# 03_-_NDP_LRA_and_BLE.net
KiCad netlist of a schematic drawn in Altium Designer
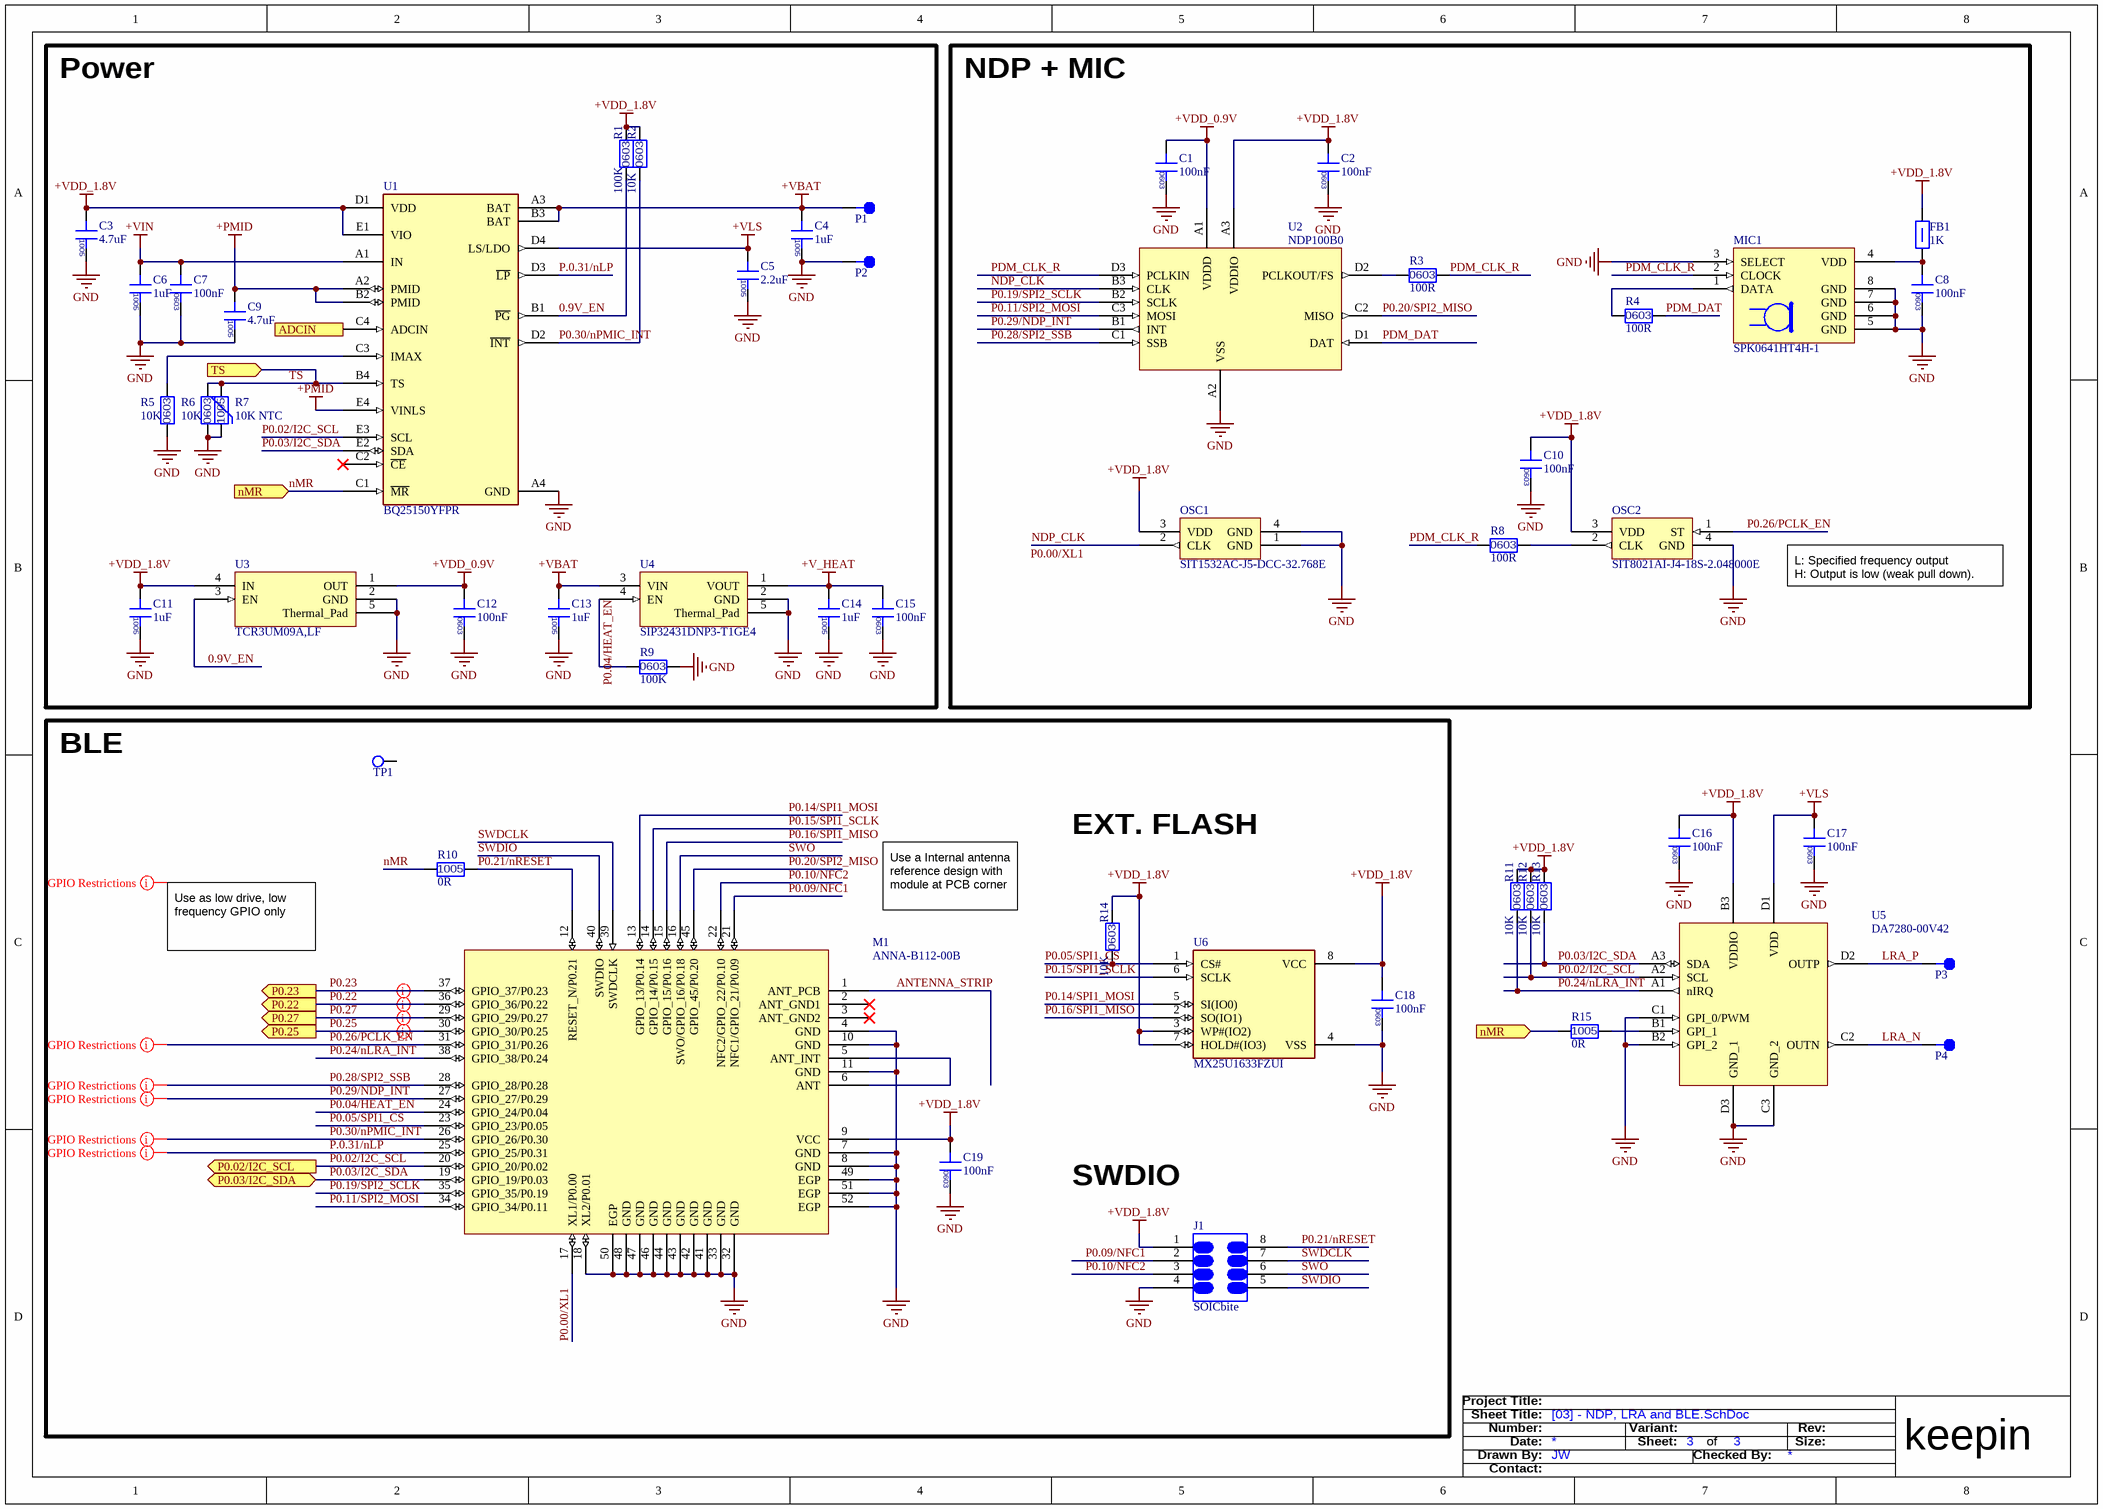
[diagram p0: [03] - NDP, LRA and BLE.SchDoc]

(export (version "E")
  (design (tool "Eeschema 10.0.6"))
  (components
    (comp (ref "C1")
      (value "100nF")
      (footprint "CAPC0603X03N")
      (description "CAP CER 0.1UF 16V X7S 0201")
      (fields
        (field (name "MANUFACTURER") "Murata")
        (field (name "MANUFACTURER PART NUMBER") "GRM033C71C104ME14D")
      )
      (libsource (lib "Schlib-master") (part "GRM033C71C104ME14D"))
    )
    (comp (ref "C2")
      (value "100nF")
      (footprint "CAPC0603X03N")
      (description "CAP CER 0.1UF 16V X7S 0201")
      (fields
        (field (name "MANUFACTURER") "Murata")
        (field (name "MANUFACTURER PART NUMBER") "GRM033C71C104ME14D")
      )
      (libsource (lib "Schlib-master") (part "GRM033C71C104ME14D"))
    )
    (comp (ref "C3")
      (value "4.7uF")
      (footprint "CAPC1005X06N")
      (description "CAP CER 4.7UF 16V X5R 0402")
      (fields (field (name "TOLERANCE") "20%") (field (name "MANUFACTURER") "Samsung"))
      (libsource (lib "Schlib-master") (part "CL05A475MO5NUNC"))
    )
    (comp (ref "C4")
      (value "1uF")
      (footprint "CAPC1005X06N")
      (description "CAP CER 1UF 16V X5R 0402")
      (fields
        (field (name "MANUFACTURER") "Samsung")
        (field (name "MANUFACTURER PART NUMBER") "CL05A105KO5NNNC")
      )
      (libsource (lib "Schlib-master") (part "CL05A105KO5NNNC"))
    )
    (comp (ref "C5")
      (value "2.2uF")
      (footprint "CAPC1005X06N")
      (description "CAP CER 2.2UF 10V X5R 0402")
      (fields
        (field (name "MANUFACTURER") "Samsung")
        (field (name "MANUFACTURER PART NUMBER") "CL05A225KP7NSB8")
      )
      (libsource (lib "Schlib-master") (part "CL05A225KP7NSB8"))
    )
    (comp (ref "C6")
      (value "1uF")
      (footprint "CAPC1005X06N")
      (description "CAP CER 1UF 16V X5R 0402")
      (fields
        (field (name "MANUFACTURER") "Samsung")
        (field (name "MANUFACTURER PART NUMBER") "CL05A105KO5NNNC")
      )
      (libsource (lib "Schlib-master") (part "CL05A105KO5NNNC"))
    )
    (comp (ref "C7")
      (value "100nF")
      (footprint "CAPC0603X03N")
      (description "CAP CER 0.1UF 16V X7S 0201")
      (fields
        (field (name "MANUFACTURER") "Murata")
        (field (name "MANUFACTURER PART NUMBER") "GRM033C71C104ME14D")
      )
      (libsource (lib "Schlib-master") (part "GRM033C71C104ME14D"))
    )
    (comp (ref "C8")
      (value "100nF")
      (footprint "CAPC0603X03N")
      (description "CAP CER 0.1UF 16V X7S 0201")
      (fields
        (field (name "MANUFACTURER") "Murata")
        (field (name "MANUFACTURER PART NUMBER") "GRM033C71C104ME14D")
      )
      (libsource (lib "Schlib-master") (part "GRM033C71C104ME14D"))
    )
    (comp (ref "C9")
      (value "4.7uF")
      (footprint "CAPC1005X06N")
      (description "CAP CER 4.7UF 16V X5R 0402")
      (fields (field (name "TOLERANCE") "20%") (field (name "MANUFACTURER") "Samsung"))
      (libsource (lib "Schlib-master") (part "CL05A475MO5NUNC"))
    )
    (comp (ref "C10")
      (value "100nF")
      (footprint "CAPC0603X03N")
      (description "CAP CER 0.1UF 16V X7S 0201")
      (fields
        (field (name "MANUFACTURER") "Murata")
        (field (name "MANUFACTURER PART NUMBER") "GRM033C71C104ME14D")
      )
      (libsource (lib "Schlib-master") (part "GRM033C71C104ME14D"))
    )
    (comp (ref "C11")
      (value "1uF")
      (footprint "CAPC1005X06N")
      (description "CAP CER 1UF 16V X5R 0402")
      (fields
        (field (name "MANUFACTURER") "Samsung")
        (field (name "MANUFACTURER PART NUMBER") "CL05A105KO5NNNC")
      )
      (libsource (lib "Schlib-master") (part "CL05A105KO5NNNC"))
    )
    (comp (ref "C12")
      (value "100nF")
      (footprint "CAPC0603X03N")
      (description "CAP CER 0.1UF 16V X7S 0201")
      (fields
        (field (name "MANUFACTURER") "Murata")
        (field (name "MANUFACTURER PART NUMBER") "GRM033C71C104ME14D")
      )
      (libsource (lib "Schlib-master") (part "GRM033C71C104ME14D"))
    )
    (comp (ref "C13")
      (value "1uF")
      (footprint "CAPC1005X06N")
      (description "CAP CER 1UF 16V X5R 0402")
      (fields
        (field (name "MANUFACTURER") "Samsung")
        (field (name "MANUFACTURER PART NUMBER") "CL05A105KO5NNNC")
      )
      (libsource (lib "Schlib-master") (part "CL05A105KO5NNNC"))
    )
    (comp (ref "C14")
      (value "1uF")
      (footprint "CAPC1005X06N")
      (description "CAP CER 1UF 16V X5R 0402")
      (fields
        (field (name "MANUFACTURER") "Samsung")
        (field (name "MANUFACTURER PART NUMBER") "CL05A105KO5NNNC")
      )
      (libsource (lib "Schlib-master") (part "CL05A105KO5NNNC"))
    )
    (comp (ref "C15")
      (value "100nF")
      (footprint "CAPC0603X03N")
      (description "CAP CER 0.1UF 16V X7S 0201")
      (fields
        (field (name "MANUFACTURER") "Murata")
        (field (name "MANUFACTURER PART NUMBER") "GRM033C71C104ME14D")
      )
      (libsource (lib "Schlib-master") (part "GRM033C71C104ME14D"))
    )
    (comp (ref "C16")
      (value "100nF")
      (footprint "CAPC0603X03N")
      (description "CAP CER 0.1UF 16V X7S 0201")
      (fields
        (field (name "MANUFACTURER") "Murata")
        (field (name "MANUFACTURER PART NUMBER") "GRM033C71C104ME14D")
      )
      (libsource (lib "Schlib-master") (part "GRM033C71C104ME14D"))
    )
    (comp (ref "C17")
      (value "100nF")
      (footprint "CAPC0603X03N")
      (description "CAP CER 0.1UF 16V X7S 0201")
      (fields
        (field (name "MANUFACTURER") "Murata")
        (field (name "MANUFACTURER PART NUMBER") "GRM033C71C104ME14D")
      )
      (libsource (lib "Schlib-master") (part "GRM033C71C104ME14D"))
    )
    (comp (ref "C18")
      (value "100nF")
      (footprint "CAPC0603X03N")
      (description "CAP CER 0.1UF 16V X7S 0201")
      (fields
        (field (name "MANUFACTURER") "Murata")
        (field (name "MANUFACTURER PART NUMBER") "GRM033C71C104ME14D")
      )
      (libsource (lib "Schlib-master") (part "GRM033C71C104ME14D"))
    )
    (comp (ref "C19")
      (value "100nF")
      (footprint "CAPC0603X03N")
      (description "CAP CER 0.1UF 16V X7S 0201")
      (fields
        (field (name "MANUFACTURER") "Murata")
        (field (name "MANUFACTURER PART NUMBER") "GRM033C71C104ME14D")
      )
      (libsource (lib "Schlib-master") (part "GRM033C71C104ME14D"))
    )
    (comp (ref "FB1")
      (value "1K")
      (footprint "INDC1005X05N")
      (description "FERRITE BEAD 1 KOHM 0402 1LN")
      (fields (field (name "TOLERANCE") "25%") (field (name "MANUFACTURER") "Murata"))
      (libsource (lib "Schlib") (part "BLM15HG102SN1D"))
    )
    (comp (ref "J1")
      (value "SOICbite")
      (footprint "SOICBITE")
      (fields (field (name "MANUFACTURER") "SimonMerrett"))
      (libsource (lib "Schlib-master") (part "SOICbite"))
    )
    (comp (ref "M1")
      (value "ANNA-B112-00B")
      (footprint "ANNA-B112")
      (description "RX TXRX MODULE BLUETOOTH SMD")
      (fields (field (name "MANUFACTURER") "u-blox"))
      (libsource (lib "Schlib-master") (part "ANNA-B112-00B"))
    )
    (comp (ref "MIC1")
      (value "SPK0641HT4H-1")
      (footprint "MIC_SPK0838HT4H-1")
      (description "RAMIS MIC MULTIMODE DGT TOP PORT")
      (fields (field (name "MANUFACTURER") "Knowles"))
      (libsource (lib "Schlib") (part "SPK0641HT4H-1"))
    )
    (comp (ref "OSC1")
      (value "SIT1532AC-J5-DCC-32.768E")
      (footprint "SIT1532")
      (description "MEMS OSC XO 32.7680KHZ LVCMOS")
      (fields (field (name "MANUFACTURER") "SiTime"))
      (libsource (lib "Schlib-master") (part "SIT1532AC-J5-DCC-32.768E"))
    )
    (comp (ref "OSC2")
      (value "SIT8021AI-J4-18S-2.048000E")
      (footprint "SIT1532")
      (description "MEMS OSC XO 2.0480MHZ LVCMOS SMD")
      (fields (field (name "MANUFACTURER") "SiTime"))
      (libsource (lib "Schlib-master") (part "SIT8021AI-J4-18S-2.048000E"))
    )
    (comp (ref "P1")
      (value "1x1_Octagonal_1.27")
      (footprint "1x1_OCTAGONAL_1.27")
      (libsource (lib "Schlib-master") (part "1x1_Octagonal_1.27"))
    )
    (comp (ref "P2")
      (value "1x1_Octagonal_1.27")
      (footprint "1x1_OCTAGONAL_1.27")
      (libsource (lib "Schlib-master") (part "1x1_Octagonal_1.27"))
    )
    (comp (ref "P3")
      (value "1x1_Octagonal_1.27")
      (footprint "1x1_OCTAGONAL_1.27")
      (libsource (lib "Schlib-master") (part "1x1_Octagonal_1.27"))
    )
    (comp (ref "P4")
      (value "1x1_Octagonal_1.27")
      (footprint "1x1_OCTAGONAL_1.27")
      (libsource (lib "Schlib-master") (part "1x1_Octagonal_1.27"))
    )
    (comp (ref "R1")
      (value "100K")
      (footprint "RESC0603X02N")
      (description "RES SMD 100K OHM 5% 1/20W 0201")
      (fields
        (field (name "MANUFACTURER") "Yageo")
        (field (name "MANUFACTURER PART NUMBER") "RC0201JR-07100KL")
      )
      (libsource (lib "Schlib-master") (part "RC0201JR-07100KL"))
    )
    (comp (ref "R2")
      (value "10K")
      (footprint "RESC0603X02N")
      (description "RES SMD 10K OHM 1% 1/20W 0201")
      (fields
        (field (name "MANUFACTURER") "Yageo")
        (field (name "MANUFACTURER PART NUMBER") "RC0201FR-0710KL")
      )
      (libsource (lib "Schlib-master") (part "RC0201FR-0710KL"))
    )
    (comp (ref "R3")
      (value "100R")
      (footprint "RESC0603X02N")
      (description "RES SMD 100 OHM 1% 1/20W 0201")
      (fields
        (field (name "MANUFACTURER") "Yageo")
        (field (name "MANUFACTURER PART NUMBER") "RC0201FR-07100RL")
      )
      (libsource (lib "Schlib-master") (part "RC0201FR-07100RL"))
    )
    (comp (ref "R4")
      (value "100R")
      (footprint "RESC0603X02N")
      (description "RES SMD 100 OHM 1% 1/20W 0201")
      (fields
        (field (name "MANUFACTURER") "Yageo")
        (field (name "MANUFACTURER PART NUMBER") "RC0201FR-07100RL")
      )
      (libsource (lib "Schlib-master") (part "RC0201FR-07100RL"))
    )
    (comp (ref "R5")
      (value "10K")
      (footprint "RESC0603X02N")
      (description "RES SMD 10K OHM 1% 1/20W 0201")
      (fields
        (field (name "MANUFACTURER") "Yageo")
        (field (name "MANUFACTURER PART NUMBER") "RC0201FR-0710KL")
      )
      (libsource (lib "Schlib-master") (part "RC0201FR-0710KL"))
    )
    (comp (ref "R6")
      (value "10K")
      (footprint "RESC0603X02N")
      (description "RES SMD 10K OHM 1% 1/20W 0201")
      (fields
        (field (name "MANUFACTURER") "Yageo")
        (field (name "MANUFACTURER PART NUMBER") "RC0201FR-0710KL")
      )
      (libsource (lib "Schlib-master") (part "RC0201FR-0710KL"))
    )
    (comp (ref "R7")
      (value "10K NTC")
      (footprint "NTC1005X05N")
      (description "THERMISTOR NTC 10KOHM 3380K 0402")
      (fields (field (name "TOLERANCE") "5%") (field (name "MANUFACTURER") "Murata"))
      (libsource (lib "Schlib-master") (part "NCP15XH103J03RC"))
    )
    (comp (ref "R8")
      (value "100R")
      (footprint "RESC0603X02N")
      (description "RES SMD 100 OHM 1% 1/20W 0201")
      (fields
        (field (name "MANUFACTURER") "Yageo")
        (field (name "MANUFACTURER PART NUMBER") "RC0201FR-07100RL")
      )
      (libsource (lib "Schlib-master") (part "RC0201FR-07100RL"))
    )
    (comp (ref "R9")
      (value "100K")
      (footprint "RESC0603X02N")
      (description "RES SMD 100K OHM 5% 1/20W 0201")
      (fields
        (field (name "MANUFACTURER") "Yageo")
        (field (name "MANUFACTURER PART NUMBER") "RC0201JR-07100KL")
      )
      (libsource (lib "") (part "RC0201JR-07100KL_1"))
    )
    (comp (ref "R10")
      (value "0R")
      (footprint "RESC1005X04N")
      (description "RES SMD 0 OHM JUMPER 1/16W 0402")
      (fields
        (field (name "MANUFACTURER") "Yageo")
        (field (name "MANUFACTURER PART NUMBER") "RC0402JR-070RL")
      )
      (libsource (lib "Schlib-master") (part "RC0402JR-070RL"))
    )
    (comp (ref "R11")
      (value "10K")
      (footprint "RESC0603X02N")
      (description "RES SMD 10K OHM 1% 1/20W 0201")
      (fields
        (field (name "MANUFACTURER") "Yageo")
        (field (name "MANUFACTURER PART NUMBER") "RC0201FR-0710KL")
      )
      (libsource (lib "Schlib-master") (part "RC0201FR-0710KL"))
    )
    (comp (ref "R12")
      (value "10K")
      (footprint "RESC0603X02N")
      (description "RES SMD 10K OHM 1% 1/20W 0201")
      (fields
        (field (name "MANUFACTURER") "Yageo")
        (field (name "MANUFACTURER PART NUMBER") "RC0201FR-0710KL")
      )
      (libsource (lib "Schlib-master") (part "RC0201FR-0710KL"))
    )
    (comp (ref "R13")
      (value "10K")
      (footprint "RESC0603X02N")
      (description "RES SMD 10K OHM 1% 1/20W 0201")
      (fields
        (field (name "MANUFACTURER") "Yageo")
        (field (name "MANUFACTURER PART NUMBER") "RC0201FR-0710KL")
      )
      (libsource (lib "Schlib-master") (part "RC0201FR-0710KL"))
    )
    (comp (ref "R14")
      (value "10K")
      (footprint "RESC0603X02N")
      (description "RES SMD 10K OHM 1% 1/20W 0201")
      (fields
        (field (name "MANUFACTURER") "Yageo")
        (field (name "MANUFACTURER PART NUMBER") "RC0201FR-0710KL")
      )
      (libsource (lib "Schlib-master") (part "RC0201FR-0710KL"))
    )
    (comp (ref "R15")
      (value "0R")
      (footprint "RESC1005X04N")
      (description "RES SMD 0 OHM JUMPER 1/16W 0402")
      (fields
        (field (name "MANUFACTURER") "Yageo")
        (field (name "MANUFACTURER PART NUMBER") "RC0402JR-070RL")
      )
      (libsource (lib "Schlib-master") (part "RC0402JR-070RL"))
    )
    (comp (ref "TP1")
      (value "TESTPOINT")
      (footprint "TESTPOINT_1mm")
      (description "TESTPOINT PAD")
      (libsource (lib "Schlib-master") (part "TESTPOINT"))
    )
    (comp (ref "U1")
      (value "BQ25150YFPR")
      (footprint "YFP0020ACAC")
      (description "LOW IQ LINEAR BATTERY CHARGE MAN")
      (fields (field (name "MANUFACTURER") "Texas Instruments"))
      (libsource (lib "Schlib-master") (part "BQ25150YFPR"))
    )
    (comp (ref "U2")
      (value "NDP100B0")
      (footprint "NDP100B0_BGA12C40P3X4_139X176X55")
      (description "IC NDP 32BIT 112KB SRAM WLBGA")
      (fields (field (name "MANUFACTURER") "SYNTIANT"))
      (libsource (lib "Schlib-master") (part "NDP100B0"))
    )
    (comp (ref "U3")
      (value "TCR3UM09A,LF")
      (footprint "DQN-4")
      (description "IC REG LINEAR 0.9V 300MA 4DFN")
      (fields (field (name "MANUFACTURER") "Toshiba"))
      (libsource (lib "Schlib-master") (part "TCR3UM09A,LF"))
    )
    (comp (ref "U4")
      (value "SIP32431DNP3-T1GE4")
      (footprint "SON50P160X60_HS-5N")
      (description "IC PWR SWITCH P-CHAN 1:1 4TDFN")
      (fields (field (name "MANUFACTURER") "Vishay Siliconix"))
      (libsource (lib "Schlib-master") (part "SIP32431DNP3-T1GE4"))
    )
    (comp (ref "U5")
      (value "DA7280-00V42")
      (footprint "BGA12C40P3X4_135X175X57")
      (description "LRA/ERM HAPTIC DRIVER WLCSP12")
      (fields (field (name "MANUFACTURER") "Dialog Semiconductor"))
      (libsource (lib "Schlib-master") (part "DA7280-00V42"))
    )
    (comp (ref "U6")
      (value "MX25U1633FZUI")
      (footprint "USON8_3X2")
      (description "IC FLASH 16MBIT SPI/QUAD 8USON")
      (fields (field (name "MANUFACTURER") "Macronix"))
      (libsource (lib "Schlib-master") (part "MX25U1633FZUI"))
    )
  )
  (nets
    (net (code "1") (name "+PMID") (class "Default")
      (node (ref "C9") (pin "2") (pinfunction "2_2") (pintype "passive"))
      (node (ref "U1") (pin "A2") (pinfunction "PMID_A2") (pintype "bidirectional"))
      (node (ref "U1") (pin "B2") (pinfunction "PMID_B2") (pintype "bidirectional"))
      (node (ref "U1") (pin "E4") (pinfunction "VINLS_E4") (pintype "input"))
    )
    (net (code "2") (name "+VBAT") (class "Default")
      (node (ref "C13") (pin "2") (pinfunction "2_2") (pintype "passive"))
      (node (ref "C4") (pin "2") (pinfunction "2_2") (pintype "passive"))
      (node (ref "P1") (pin "1") (pinfunction "1_1") (pintype "passive"))
      (node (ref "U1") (pin "A3") (pinfunction "BAT_A3") (pintype "power_in"))
      (node (ref "U1") (pin "B3") (pinfunction "BAT_B3") (pintype "power_in"))
      (node (ref "U4") (pin "3") (pinfunction "VIN_3") (pintype "power_in"))
    )
    (net (code "3") (name "+VDD_0.9V") (class "Default")
      (node (ref "C1") (pin "2") (pinfunction "2_2") (pintype "passive"))
      (node (ref "C12") (pin "2") (pinfunction "2_2") (pintype "passive"))
      (node (ref "U2") (pin "A1") (pinfunction "VDDD_A1") (pintype "power_in"))
      (node (ref "U3") (pin "1") (pinfunction "OUT_1") (pintype "power_in"))
    )
    (net (code "4") (name "+VDD_1.8V") (class "Default")
      (node (ref "C10") (pin "2") (pinfunction "2_2") (pintype "passive"))
      (node (ref "C11") (pin "2") (pinfunction "2_2") (pintype "passive"))
      (node (ref "C16") (pin "2") (pinfunction "2_2") (pintype "passive"))
      (node (ref "C18") (pin "2") (pinfunction "2_2") (pintype "passive"))
      (node (ref "C19") (pin "2") (pinfunction "2_2") (pintype "passive"))
      (node (ref "C2") (pin "2") (pinfunction "2_2") (pintype "passive"))
      (node (ref "C3") (pin "2") (pinfunction "2_2") (pintype "passive"))
      (node (ref "FB1") (pin "1") (pinfunction "1_1") (pintype "passive"))
      (node (ref "J1") (pin "1") (pinfunction "1_1") (pintype "passive"))
      (node (ref "M1") (pin "9") (pinfunction "VCC_9") (pintype "power_in"))
      (node (ref "OSC1") (pin "3") (pinfunction "VDD_3") (pintype "power_in"))
      (node (ref "OSC2") (pin "3") (pinfunction "VDD_3") (pintype "power_in"))
      (node (ref "R1") (pin "2") (pinfunction "2_2") (pintype "passive"))
      (node (ref "R11") (pin "2") (pinfunction "2_2") (pintype "passive"))
      (node (ref "R12") (pin "2") (pinfunction "2_2") (pintype "passive"))
      (node (ref "R13") (pin "2") (pinfunction "2_2") (pintype "passive"))
      (node (ref "R14") (pin "2") (pinfunction "2_2") (pintype "passive"))
      (node (ref "R2") (pin "2") (pinfunction "2_2") (pintype "passive"))
      (node (ref "U1") (pin "D1") (pinfunction "VDD_D1") (pintype "power_in"))
      (node (ref "U1") (pin "E1") (pinfunction "VIO_E1") (pintype "power_in"))
      (node (ref "U2") (pin "A3") (pinfunction "VDDIO_A3") (pintype "power_in"))
      (node (ref "U3") (pin "4") (pinfunction "IN_4") (pintype "power_in"))
      (node (ref "U5") (pin "B3") (pinfunction "VDDIO_B3") (pintype "power_in"))
      (node (ref "U6") (pin "3") (pinfunction "WP#(IO2)_3") (pintype "bidirectional"))
      (node (ref "U6") (pin "7") (pinfunction "HOLD#(IO3)_7") (pintype "bidirectional"))
      (node (ref "U6") (pin "8") (pinfunction "VCC_8") (pintype "power_in"))
    )
    (net (code "5") (name "+VIN") (class "Default")
      (node (ref "C6") (pin "2") (pinfunction "2_2") (pintype "passive"))
      (node (ref "C7") (pin "2") (pinfunction "2_2") (pintype "passive"))
      (node (ref "U1") (pin "A1") (pinfunction "IN_A1") (pintype "power_in"))
    )
    (net (code "6") (name "+VLS") (class "Default")
      (node (ref "C17") (pin "2") (pinfunction "2_2") (pintype "passive"))
      (node (ref "C5") (pin "2") (pinfunction "2_2") (pintype "passive"))
      (node (ref "U1") (pin "D4") (pinfunction "LS/LDO_D4") (pintype "output"))
      (node (ref "U5") (pin "D1") (pinfunction "VDD_D1") (pintype "power_in"))
    )
    (net (code "7") (name "+V_HEAT") (class "Default")
      (node (ref "C14") (pin "2") (pinfunction "2_2") (pintype "passive"))
      (node (ref "C15") (pin "2") (pinfunction "2_2") (pintype "passive"))
      (node (ref "U4") (pin "1") (pinfunction "VOUT_1") (pintype "power_in"))
    )
    (net (code "8") (name "/0.9V_EN") (class "Default")
      (node (ref "R1") (pin "1") (pinfunction "1_1") (pintype "passive"))
      (node (ref "U1") (pin "B1") (pinfunction "~{PG}_B1") (pintype "output"))
      (node (ref "U3") (pin "3") (pinfunction "EN_3") (pintype "input"))
    )
    (net (code "9") (name "/ADCIN") (class "Default")
      (node (ref "U1") (pin "C4") (pinfunction "ADCIN_C4") (pintype "input"))
    )
    (net (code "10") (name "/ANTENNA_STRIP") (class "Default")
      (node (ref "M1") (pin "1") (pinfunction "ANT_PCB_1") (pintype "passive"))
    )
    (net (code "11") (name "/LRA_N") (class "Default")
      (node (ref "P4") (pin "1") (pinfunction "1_1") (pintype "passive"))
      (node (ref "U5") (pin "C2") (pinfunction "OUTN_C2") (pintype "output"))
    )
    (net (code "12") (name "/LRA_P") (class "Default")
      (node (ref "P3") (pin "1") (pinfunction "1_1") (pintype "passive"))
      (node (ref "U5") (pin "D2") (pinfunction "OUTP_D2") (pintype "output"))
    )
    (net (code "13") (name "/NDP_CLK") (class "Default")
      (node (ref "M1") (pin "17") (pinfunction "XL1/P0.00_17") (pintype "bidirectional"))
      (node (ref "OSC1") (pin "2") (pinfunction "CLK_2") (pintype "output"))
      (node (ref "U2") (pin "B3") (pinfunction "CLK_B3") (pintype "input"))
    )
    (net (code "14") (name "/P.0.31{slash}nLP") (class "Default")
      (node (ref "M1") (pin "25") (pinfunction "GPIO_25/P0.31_25") (pintype "bidirectional"))
      (node (ref "U1") (pin "D3") (pinfunction "~{LP}_D3") (pintype "output"))
    )
    (net (code "15") (name "/P0.02{slash}I2C_SCL") (class "Default")
      (node (ref "M1") (pin "20") (pinfunction "GPIO_20/P0.02_20") (pintype "bidirectional"))
      (node (ref "R12") (pin "1") (pinfunction "1_1") (pintype "passive"))
      (node (ref "U1") (pin "E3") (pinfunction "SCL_E3") (pintype "input"))
      (node (ref "U5") (pin "A2") (pinfunction "SCL_A2") (pintype "input"))
    )
    (net (code "16") (name "/P0.03{slash}I2C_SDA") (class "Default")
      (node (ref "M1") (pin "19") (pinfunction "GPIO_19/P0.03_19") (pintype "bidirectional"))
      (node (ref "R13") (pin "1") (pinfunction "1_1") (pintype "passive"))
      (node (ref "U1") (pin "E2") (pinfunction "SDA_E2") (pintype "bidirectional"))
      (node (ref "U5") (pin "A3") (pinfunction "SDA_A3") (pintype "bidirectional"))
    )
    (net (code "17") (name "/P0.04{slash}HEAT_EN") (class "Default")
      (node (ref "M1") (pin "24") (pinfunction "GPIO_24/P0.04_24") (pintype "bidirectional"))
      (node (ref "R9") (pin "1") (pinfunction "1_1") (pintype "passive"))
      (node (ref "U4") (pin "4") (pinfunction "EN_4") (pintype "input"))
    )
    (net (code "18") (name "/P0.05{slash}SPI1_CS") (class "Default")
      (node (ref "M1") (pin "23") (pinfunction "GPIO_23/P0.05_23") (pintype "bidirectional"))
      (node (ref "R14") (pin "1") (pinfunction "1_1") (pintype "passive"))
      (node (ref "U6") (pin "1") (pinfunction "CS#_1") (pintype "input"))
    )
    (net (code "19") (name "/P0.09{slash}NFC1") (class "Default")
      (node (ref "J1") (pin "2") (pinfunction "2_2") (pintype "passive"))
      (node (ref "M1") (pin "21") (pinfunction "NFC1/GPIO_21/P0.09_21") (pintype "bidirectional"))
    )
    (net (code "20") (name "/P0.10{slash}NFC2") (class "Default")
      (node (ref "J1") (pin "3") (pinfunction "3_3") (pintype "passive"))
      (node (ref "M1") (pin "22") (pinfunction "NFC2/GPIO_22/P0.10_22") (pintype "bidirectional"))
    )
    (net (code "21") (name "/P0.11{slash}SPI2_MOSI") (class "Default")
      (node (ref "M1") (pin "34") (pinfunction "GPIO_34/P0.11_34") (pintype "bidirectional"))
      (node (ref "U2") (pin "C3") (pinfunction "MOSI_C3") (pintype "input"))
    )
    (net (code "22") (name "/P0.14{slash}SPI1_MOSI") (class "Default")
      (node (ref "M1") (pin "13") (pinfunction "GPIO_13/P0.14_13") (pintype "bidirectional"))
      (node (ref "U6") (pin "5") (pinfunction "SI(IO0)_5") (pintype "bidirectional"))
    )
    (net (code "23") (name "/P0.15{slash}SPI1_SCLK") (class "Default")
      (node (ref "M1") (pin "14") (pinfunction "GPIO_14/P0.15_14") (pintype "bidirectional"))
      (node (ref "U6") (pin "6") (pinfunction "SCLK_6") (pintype "input"))
    )
    (net (code "24") (name "/P0.16{slash}SPI1_MISO") (class "Default")
      (node (ref "M1") (pin "15") (pinfunction "GPIO_15/P0.16_15") (pintype "bidirectional"))
      (node (ref "U6") (pin "2") (pinfunction "SO(IO1)_2") (pintype "bidirectional"))
    )
    (net (code "25") (name "/P0.19{slash}SPI2_SCLK") (class "Default")
      (node (ref "M1") (pin "35") (pinfunction "GPIO_35/P0.19_35") (pintype "bidirectional"))
      (node (ref "U2") (pin "B2") (pinfunction "SCLK_B2") (pintype "input"))
    )
    (net (code "26") (name "/P0.20{slash}SPI2_MISO") (class "Default")
      (node (ref "M1") (pin "45") (pinfunction "GPIO_45/P0.20_45") (pintype "bidirectional"))
      (node (ref "U2") (pin "C2") (pinfunction "MISO_C2") (pintype "output"))
    )
    (net (code "27") (name "/P0.21{slash}nRESET") (class "Default")
      (node (ref "J1") (pin "8") (pinfunction "8_8") (pintype "passive"))
      (node (ref "M1") (pin "12") (pinfunction "RESET_N/P0.21_12") (pintype "bidirectional"))
      (node (ref "R10") (pin "2") (pinfunction "2_2") (pintype "passive"))
    )
    (net (code "28") (name "/P0.22") (class "Default")
      (node (ref "M1") (pin "36") (pinfunction "GPIO_36/P0.22_36") (pintype "bidirectional"))
    )
    (net (code "29") (name "/P0.23") (class "Default")
      (node (ref "M1") (pin "37") (pinfunction "GPIO_37/P0.23_37") (pintype "bidirectional"))
    )
    (net (code "30") (name "/P0.24{slash}nLRA_INT") (class "Default")
      (node (ref "M1") (pin "38") (pinfunction "GPIO_38/P0.24_38") (pintype "bidirectional"))
      (node (ref "R11") (pin "1") (pinfunction "1_1") (pintype "passive"))
      (node (ref "U5") (pin "A1") (pinfunction "nIRQ_A1") (pintype "output"))
    )
    (net (code "31") (name "/P0.25") (class "Default")
      (node (ref "M1") (pin "30") (pinfunction "GPIO_30/P0.25_30") (pintype "bidirectional"))
    )
    (net (code "32") (name "/P0.26{slash}PCLK_EN") (class "Default")
      (node (ref "M1") (pin "31") (pinfunction "GPIO_31/P0.26_31") (pintype "bidirectional"))
      (node (ref "OSC2") (pin "1") (pinfunction "ST_1") (pintype "input"))
    )
    (net (code "33") (name "/P0.27") (class "Default")
      (node (ref "M1") (pin "29") (pinfunction "GPIO_29/P0.27_29") (pintype "bidirectional"))
    )
    (net (code "34") (name "/P0.28{slash}SPI2_SSB") (class "Default")
      (node (ref "M1") (pin "28") (pinfunction "GPIO_28/P0.28_28") (pintype "bidirectional"))
      (node (ref "U2") (pin "C1") (pinfunction "SSB_C1") (pintype "input"))
    )
    (net (code "35") (name "/P0.29{slash}NDP_INT") (class "Default")
      (node (ref "M1") (pin "27") (pinfunction "GPIO_27/P0.29_27") (pintype "bidirectional"))
      (node (ref "U2") (pin "B1") (pinfunction "INT_B1") (pintype "output"))
    )
    (net (code "36") (name "/P0.30{slash}nPMIC_INT") (class "Default")
      (node (ref "M1") (pin "26") (pinfunction "GPIO_26/P0.30_26") (pintype "bidirectional"))
      (node (ref "R2") (pin "1") (pinfunction "1_1") (pintype "passive"))
      (node (ref "U1") (pin "D2") (pinfunction "~{INT}_D2") (pintype "output"))
    )
    (net (code "37") (name "/PDM_CLK_R") (class "Default")
      (node (ref "MIC1") (pin "2") (pinfunction "CLOCK_2") (pintype "input"))
      (node (ref "R3") (pin "2") (pinfunction "2_2") (pintype "passive"))
      (node (ref "R8") (pin "1") (pinfunction "1_1") (pintype "passive"))
      (node (ref "U2") (pin "D3") (pinfunction "PCLKIN_D3") (pintype "input"))
    )
    (net (code "38") (name "/PDM_DAT") (class "Default")
      (node (ref "R4") (pin "2") (pinfunction "2_2") (pintype "passive"))
      (node (ref "U2") (pin "D1") (pinfunction "DAT_D1") (pintype "input"))
    )
    (net (code "39") (name "/SWDCLK") (class "Default")
      (node (ref "J1") (pin "7") (pinfunction "7_7") (pintype "passive"))
      (node (ref "M1") (pin "39") (pinfunction "SWDCLK_39") (pintype "input"))
    )
    (net (code "40") (name "/SWDIO") (class "Default")
      (node (ref "J1") (pin "5") (pinfunction "5_5") (pintype "passive"))
      (node (ref "M1") (pin "40") (pinfunction "SWDIO_40") (pintype "bidirectional"))
    )
    (net (code "41") (name "/SWO") (class "Default")
      (node (ref "J1") (pin "6") (pinfunction "6_6") (pintype "passive"))
      (node (ref "M1") (pin "16") (pinfunction "SWO/GPIO_16/P0.18_16") (pintype "bidirectional"))
    )
    (net (code "42") (name "/TS") (class "Default")
      (node (ref "R6") (pin "2") (pinfunction "2_2") (pintype "passive"))
      (node (ref "R7") (pin "2") (pinfunction "2_2") (pintype "passive"))
      (node (ref "U1") (pin "B4") (pinfunction "TS_B4") (pintype "input"))
    )
    (net (code "43") (name "/nMR") (class "Default")
      (node (ref "R10") (pin "1") (pinfunction "1_1") (pintype "passive"))
      (node (ref "R15") (pin "1") (pinfunction "1_1") (pintype "passive"))
      (node (ref "U1") (pin "C1") (pinfunction "~{MR}_C1") (pintype "input"))
    )
    (net (code "44") (name "GND") (class "Default")
      (node (ref "C1") (pin "1") (pinfunction "1_1") (pintype "passive"))
      (node (ref "C10") (pin "1") (pinfunction "1_1") (pintype "passive"))
      (node (ref "C11") (pin "1") (pinfunction "1_1") (pintype "passive"))
      (node (ref "C12") (pin "1") (pinfunction "1_1") (pintype "passive"))
      (node (ref "C13") (pin "1") (pinfunction "1_1") (pintype "passive"))
      (node (ref "C14") (pin "1") (pinfunction "1_1") (pintype "passive"))
      (node (ref "C15") (pin "1") (pinfunction "1_1") (pintype "passive"))
      (node (ref "C16") (pin "1") (pinfunction "1_1") (pintype "passive"))
      (node (ref "C17") (pin "1") (pinfunction "1_1") (pintype "passive"))
      (node (ref "C18") (pin "1") (pinfunction "1_1") (pintype "passive"))
      (node (ref "C19") (pin "1") (pinfunction "1_1") (pintype "passive"))
      (node (ref "C2") (pin "1") (pinfunction "1_1") (pintype "passive"))
      (node (ref "C3") (pin "1") (pinfunction "1_1") (pintype "passive"))
      (node (ref "C4") (pin "1") (pinfunction "1_1") (pintype "passive"))
      (node (ref "C5") (pin "1") (pinfunction "1_1") (pintype "passive"))
      (node (ref "C6") (pin "1") (pinfunction "1_1") (pintype "passive"))
      (node (ref "C7") (pin "1") (pinfunction "1_1") (pintype "passive"))
      (node (ref "C8") (pin "1") (pinfunction "1_1") (pintype "passive"))
      (node (ref "C9") (pin "1") (pinfunction "1_1") (pintype "passive"))
      (node (ref "J1") (pin "4") (pinfunction "4_4") (pintype "passive"))
      (node (ref "M1") (pin "10") (pinfunction "GND_10") (pintype "power_in"))
      (node (ref "M1") (pin "11") (pinfunction "GND_11") (pintype "power_in"))
      (node (ref "M1") (pin "18") (pinfunction "XL2/P0.01_18") (pintype "bidirectional"))
      (node (ref "M1") (pin "32") (pinfunction "GND_32") (pintype "power_in"))
      (node (ref "M1") (pin "33") (pinfunction "GND_33") (pintype "power_in"))
      (node (ref "M1") (pin "4") (pinfunction "GND_4") (pintype "power_in"))
      (node (ref "M1") (pin "41") (pinfunction "GND_41") (pintype "power_in"))
      (node (ref "M1") (pin "42") (pinfunction "GND_42") (pintype "power_in"))
      (node (ref "M1") (pin "43") (pinfunction "GND_43") (pintype "power_in"))
      (node (ref "M1") (pin "44") (pinfunction "GND_44") (pintype "power_in"))
      (node (ref "M1") (pin "46") (pinfunction "GND_46") (pintype "power_in"))
      (node (ref "M1") (pin "47") (pinfunction "GND_47") (pintype "power_in"))
      (node (ref "M1") (pin "48") (pinfunction "GND_48") (pintype "power_in"))
      (node (ref "M1") (pin "49") (pinfunction "EGP_49") (pintype "power_in"))
      (node (ref "M1") (pin "50") (pinfunction "EGP_50") (pintype "power_in"))
      (node (ref "M1") (pin "51") (pinfunction "EGP_51") (pintype "power_in"))
      (node (ref "M1") (pin "52") (pinfunction "EGP_52") (pintype "power_in"))
      (node (ref "M1") (pin "7") (pinfunction "GND_7") (pintype "power_in"))
      (node (ref "M1") (pin "8") (pinfunction "GND_8") (pintype "power_in"))
      (node (ref "MIC1") (pin "3") (pinfunction "SELECT_3") (pintype "input"))
      (node (ref "MIC1") (pin "5") (pinfunction "GND_5") (pintype "power_in"))
      (node (ref "MIC1") (pin "6") (pinfunction "GND_6") (pintype "power_in"))
      (node (ref "MIC1") (pin "7") (pinfunction "GND_7") (pintype "power_in"))
      (node (ref "MIC1") (pin "8") (pinfunction "GND_8") (pintype "power_in"))
      (node (ref "OSC1") (pin "1") (pinfunction "GND_1") (pintype "power_in"))
      (node (ref "OSC1") (pin "4") (pinfunction "GND_4") (pintype "power_in"))
      (node (ref "OSC2") (pin "4") (pinfunction "GND_4") (pintype "power_in"))
      (node (ref "P2") (pin "1") (pinfunction "1_1") (pintype "passive"))
      (node (ref "R5") (pin "1") (pinfunction "1_1") (pintype "passive"))
      (node (ref "R6") (pin "1") (pinfunction "1_1") (pintype "passive"))
      (node (ref "R7") (pin "1") (pinfunction "1_1") (pintype "passive"))
      (node (ref "R9") (pin "2") (pinfunction "2_2") (pintype "passive"))
      (node (ref "U1") (pin "A4") (pinfunction "GND_A4") (pintype "power_in"))
      (node (ref "U2") (pin "A2") (pinfunction "VSS_A2") (pintype "power_in"))
      (node (ref "U3") (pin "2") (pinfunction "GND_2") (pintype "power_in"))
      (node (ref "U3") (pin "5") (pinfunction "Thermal_Pad_5") (pintype "passive"))
      (node (ref "U4") (pin "2") (pinfunction "GND_2") (pintype "power_in"))
      (node (ref "U4") (pin "5") (pinfunction "Thermal_Pad_5") (pintype "power_in"))
      (node (ref "U5") (pin "B2") (pinfunction "GPI_2_B2") (pintype "input"))
      (node (ref "U5") (pin "C1") (pinfunction "GPI_0/PWM_C1") (pintype "input"))
      (node (ref "U5") (pin "C3") (pinfunction "GND_2_C3") (pintype "power_in"))
      (node (ref "U5") (pin "D3") (pinfunction "GND_1_D3") (pintype "power_in"))
      (node (ref "U6") (pin "4") (pinfunction "VSS_4") (pintype "power_in"))
    )
    (net (code "45") (name "Net-(M1-ANT)") (class "Default")
      (node (ref "M1") (pin "5") (pinfunction "ANT_INT_5") (pintype "passive"))
      (node (ref "M1") (pin "6") (pinfunction "ANT_6") (pintype "passive"))
    )
    (net (code "46") (name "Net-(MIC1-DATA)") (class "Default")
      (node (ref "MIC1") (pin "1") (pinfunction "DATA_1") (pintype "output"))
      (node (ref "R4") (pin "1") (pinfunction "1_1") (pintype "passive"))
    )
    (net (code "47") (name "Net-(MIC1-VDD)") (class "Default")
      (node (ref "C8") (pin "2") (pinfunction "2_2") (pintype "passive"))
      (node (ref "FB1") (pin "2") (pinfunction "2_2") (pintype "passive"))
      (node (ref "MIC1") (pin "4") (pinfunction "VDD_4") (pintype "power_in"))
    )
    (net (code "48") (name "Net-(OSC2-CLK)") (class "Default")
      (node (ref "OSC2") (pin "2") (pinfunction "CLK_2") (pintype "output"))
      (node (ref "R8") (pin "2") (pinfunction "2_2") (pintype "passive"))
    )
    (net (code "49") (name "Net-(U1-IMAX)") (class "Default")
      (node (ref "R5") (pin "2") (pinfunction "2_2") (pintype "passive"))
      (node (ref "U1") (pin "C3") (pinfunction "IMAX_C3") (pintype "input"))
    )
    (net (code "50") (name "Net-(U2-PCLKOUT{slash}FS)") (class "Default")
      (node (ref "R3") (pin "1") (pinfunction "1_1") (pintype "passive"))
      (node (ref "U2") (pin "D2") (pinfunction "PCLKOUT/FS_D2") (pintype "output"))
    )
    (net (code "51") (name "Net-(U5-GPI_1)") (class "Default")
      (node (ref "R15") (pin "2") (pinfunction "2_2") (pintype "passive"))
      (node (ref "U5") (pin "B1") (pinfunction "GPI_1_B1") (pintype "input"))
    )
    (net (code "52") (name "unconnected-(M1-ANT_GND1-Pad2)") (class "Default")
      (node (ref "M1") (pin "2") (pinfunction "ANT_GND1_2") (pintype "passive+no_connect"))
    )
    (net (code "53") (name "unconnected-(M1-ANT_GND2-Pad3)") (class "Default")
      (node (ref "M1") (pin "3") (pinfunction "ANT_GND2_3") (pintype "passive+no_connect"))
    )
    (net (code "54") (name "unconnected-(TP1-Pad1)") (class "Default")
      (node (ref "TP1") (pin "1") (pinfunction "1_1") (pintype "passive"))
    )
    (net (code "55") (name "unconnected-(U1-~{CE}-PadC2)") (class "Default")
      (node (ref "U1") (pin "C2") (pinfunction "~{CE}_C2") (pintype "input+no_connect"))
    )
  )
)
